# BendulumClockBoard.net
KiCad netlist of a schematic drawn in EAGLE
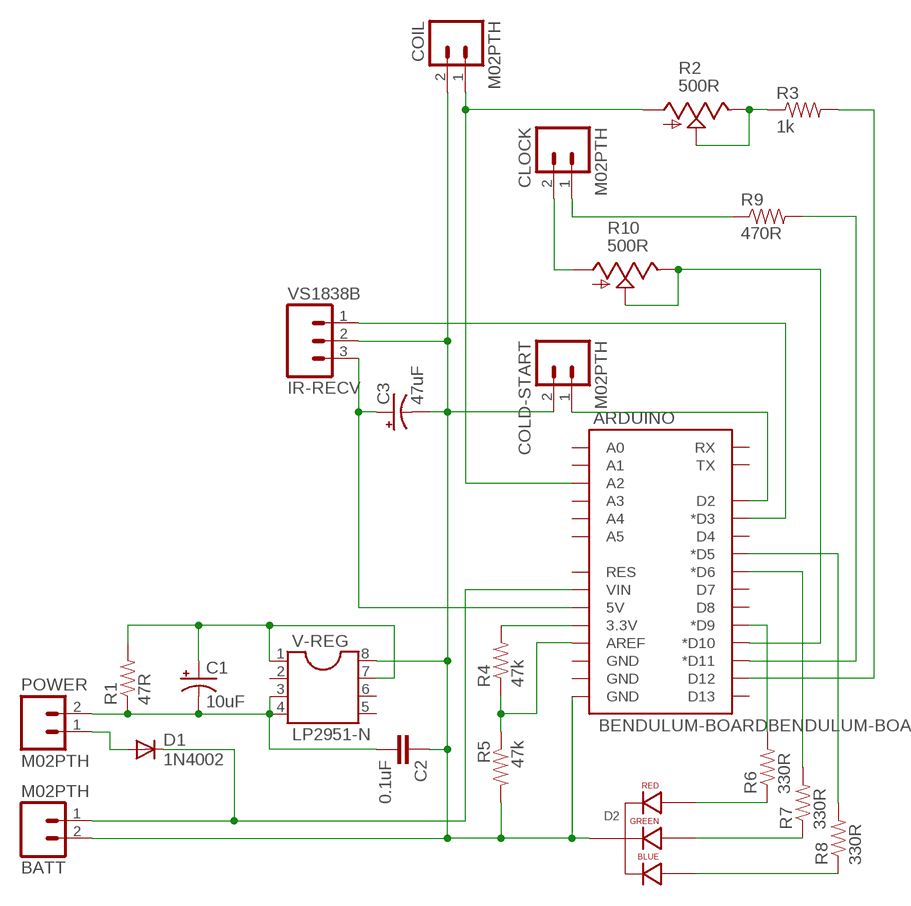
[diagram p0: schematic, sheet 1]

(export (version "E")
  (design (tool "Eeschema 10.0.6"))
  (components
    (comp (ref "ARDUINO")
      (value "BENDULUM-BOARDBENDULUM-BOARD-A")
      (footprint "eagle-import:BENDULUM-BOARD")
      (libsource (lib "eagle-import") (part "BENDULUM-BOARDBENDULUM-BOARD-A"))
    )
    (comp (ref "BATT")
      (value "M02PTH")
      (footprint "eagle-import:1X02")
      (libsource (lib "eagle-import") (part "M02PTH"))
    )
    (comp (ref "C1")
      (value "10uF")
      (footprint "eagle-import:CPOL-RADIAL-10UF-25V")
      (libsource (lib "eagle-import") (part "10UF-25V-20%(PTH)"))
    )
    (comp (ref "C2")
      (value "0.1uF")
      (footprint "eagle-import:CAP-PTH-SMALL")
      (libsource (lib "eagle-import") (part "CAPPTH"))
    )
    (comp (ref "C3")
      (value "47uF")
      (footprint "eagle-import:CPOL-RADIAL-10UF-25V")
      (libsource (lib "eagle-import") (part "10UF-25V-20%(PTH)"))
    )
    (comp (ref "CLOCK")
      (value "M02PTH")
      (footprint "eagle-import:1X02")
      (libsource (lib "eagle-import") (part "M02PTH"))
    )
    (comp (ref "COIL")
      (value "M02PTH")
      (footprint "eagle-import:1X02")
      (libsource (lib "eagle-import") (part "M02PTH"))
    )
    (comp (ref "COLD-START")
      (value "M02PTH")
      (footprint "eagle-import:1X02")
      (libsource (lib "eagle-import") (part "M02PTH"))
    )
    (comp (ref "D1")
      (value "1N4002")
      (footprint "eagle-import:DIODE-1N4001-KIT")
      (libsource (lib "eagle-import") (part "DIODE"))
    )
    (comp (ref "D2")
      (value "LED-RGB-CC-THRUDIFFUSE")
      (footprint "eagle-import:LED-RGB-THRU")
      (libsource (lib "eagle-import") (part "LED-RGB-CC-THRUDIFFUSE"))
    )
    (comp (ref "IR-RECV")
      (value "VS1838B")
      (footprint "eagle-import:1X03")
      (libsource (lib "eagle-import") (part "M03PTH"))
    )
    (comp (ref "POWER")
      (value "M02PTH")
      (footprint "eagle-import:1X02")
      (libsource (lib "eagle-import") (part "M02PTH"))
    )
    (comp (ref "R1")
      (value "47R")
      (footprint "eagle-import:AXIAL-0.4")
      (libsource (lib "eagle-import") (part "RESISTORPTH-1/4W"))
    )
    (comp (ref "R2")
      (value "500R")
      (footprint "eagle-import:S64Y")
      (libsource (lib "eagle-import") (part "TRIM_US-S64Y"))
    )
    (comp (ref "R3")
      (value "1k")
      (footprint "eagle-import:AXIAL-0.4")
      (libsource (lib "eagle-import") (part "RESISTORPTH-1/4W"))
    )
    (comp (ref "R4")
      (value "47k")
      (footprint "eagle-import:AXIAL-0.4")
      (libsource (lib "eagle-import") (part "RESISTORPTH-1/4W"))
    )
    (comp (ref "R5")
      (value "47k")
      (footprint "eagle-import:AXIAL-0.4")
      (libsource (lib "eagle-import") (part "RESISTORPTH-1/4W"))
    )
    (comp (ref "R6")
      (value "330R")
      (footprint "eagle-import:AXIAL-0.4")
      (libsource (lib "eagle-import") (part "RESISTORPTH-1/4W"))
    )
    (comp (ref "R7")
      (value "330R")
      (footprint "eagle-import:AXIAL-0.4")
      (libsource (lib "eagle-import") (part "RESISTORPTH-1/4W"))
    )
    (comp (ref "R8")
      (value "330R")
      (footprint "eagle-import:AXIAL-0.4")
      (libsource (lib "eagle-import") (part "RESISTORPTH-1/4W"))
    )
    (comp (ref "R9")
      (value "470R")
      (footprint "eagle-import:AXIAL-0.4")
      (libsource (lib "eagle-import") (part "RESISTORPTH-1/4W"))
    )
    (comp (ref "R10")
      (value "500R")
      (footprint "eagle-import:S64Y")
      (libsource (lib "eagle-import") (part "TRIM_US-S64Y"))
    )
    (comp (ref "V-REG")
      (value "LP2951-N")
      (footprint "eagle-import:SOCKET-08")
      (libsource (lib "eagle-import") (part "LP2951-N"))
    )
  )
  (nets
    (net (code "1") (name "Net-(ARDUINO-*D3)") (class "Default")
      (node (ref "ARDUINO") (pin "D3") (pinfunction "*D3_D3") (pintype "bidirectional"))
      (node (ref "IR-RECV") (pin "1") (pinfunction "1_1") (pintype "passive"))
    )
    (net (code "2") (name "Net-(ARDUINO-*D5)") (class "Default")
      (node (ref "ARDUINO") (pin "D5") (pinfunction "*D5_D5") (pintype "bidirectional"))
      (node (ref "R8") (pin "P$2") (pinfunction "2_P$2") (pintype "passive"))
    )
    (net (code "3") (name "Net-(ARDUINO-*D6)") (class "Default")
      (node (ref "ARDUINO") (pin "D6") (pinfunction "*D6_D6") (pintype "bidirectional"))
      (node (ref "R7") (pin "P$2") (pinfunction "2_P$2") (pintype "passive"))
    )
    (net (code "4") (name "Net-(ARDUINO-*D9)") (class "Default")
      (node (ref "ARDUINO") (pin "D9") (pinfunction "*D9_D9") (pintype "bidirectional"))
      (node (ref "R6") (pin "P$2") (pinfunction "2_P$2") (pintype "passive"))
    )
    (net (code "5") (name "Net-(ARDUINO-*D10)") (class "Default")
      (node (ref "ARDUINO") (pin "D10") (pinfunction "*D10_D10") (pintype "bidirectional"))
      (node (ref "R10") (pin "E") (pinfunction "E_E") (pintype "passive"))
      (node (ref "R10") (pin "S") (pinfunction "S_S") (pintype "passive"))
    )
    (net (code "6") (name "Net-(ARDUINO-*D11)") (class "Default")
      (node (ref "ARDUINO") (pin "D11") (pinfunction "*D11_D11") (pintype "bidirectional"))
      (node (ref "R9") (pin "P$2") (pinfunction "2_P$2") (pintype "passive"))
    )
    (net (code "7") (name "Net-(ARDUINO-PadA2)") (class "Default")
      (node (ref "ARDUINO") (pin "A2") (pinfunction "A2_A2") (pintype "bidirectional"))
      (node (ref "COIL") (pin "1") (pinfunction "1_1") (pintype "passive"))
      (node (ref "R2") (pin "A") (pinfunction "A_A") (pintype "passive"))
    )
    (net (code "8") (name "Net-(ARDUINO-PadD2)") (class "Default")
      (node (ref "ARDUINO") (pin "D2") (pinfunction "D2_D2") (pintype "bidirectional"))
      (node (ref "COLD-START") (pin "1") (pinfunction "1_1") (pintype "passive"))
    )
    (net (code "9") (name "Net-(ARDUINO-PadVIN)") (class "Default")
      (node (ref "ARDUINO") (pin "VIN") (pinfunction "VIN_VIN") (pintype "bidirectional"))
      (node (ref "BATT") (pin "1") (pinfunction "1_1") (pintype "passive"))
      (node (ref "D1") (pin "C") (pinfunction "C_C") (pintype "passive"))
    )
    (net (code "10") (name "Net-(C1-+)") (class "Default")
      (node (ref "C1") (pin "1") (pinfunction "+_1") (pintype "passive"))
      (node (ref "R1") (pin "P$2") (pinfunction "2_P$2") (pintype "passive"))
      (node (ref "V-REG") (pin "1") (pinfunction "OUTPUT_1") (pintype "passive"))
      (node (ref "V-REG") (pin "7") (pinfunction "FEEDBACK_7") (pintype "passive"))
    )
    (net (code "11") (name "Net-(C1--)") (class "Default")
      (node (ref "C1") (pin "2") (pinfunction "-_2") (pintype "passive"))
      (node (ref "C2") (pin "2") (pinfunction "2_2") (pintype "passive"))
      (node (ref "POWER") (pin "2") (pinfunction "2_2") (pintype "passive"))
      (node (ref "R1") (pin "P$1") (pinfunction "1_P$1") (pintype "passive"))
      (node (ref "V-REG") (pin "3") (pinfunction "SHUTDOWN_3") (pintype "passive"))
      (node (ref "V-REG") (pin "4") (pinfunction "GND_4") (pintype "passive"))
    )
    (net (code "12") (name "Net-(C3-+)") (class "Default")
      (node (ref "ARDUINO") (pin "5V") (pinfunction "5V_5V") (pintype "bidirectional"))
      (node (ref "C3") (pin "1") (pinfunction "+_1") (pintype "passive"))
      (node (ref "IR-RECV") (pin "3") (pinfunction "3_3") (pintype "passive"))
    )
    (net (code "13") (name "Net-(C3--)") (class "Default")
      (node (ref "ARDUINO") (pin "GND@0") (pinfunction "GND_GND@0") (pintype "bidirectional"))
      (node (ref "BATT") (pin "2") (pinfunction "2_2") (pintype "passive"))
      (node (ref "C2") (pin "1") (pinfunction "1_1") (pintype "passive"))
      (node (ref "C3") (pin "2") (pinfunction "-_2") (pintype "passive"))
      (node (ref "COIL") (pin "2") (pinfunction "2_2") (pintype "passive"))
      (node (ref "COLD-START") (pin "2") (pinfunction "2_2") (pintype "passive"))
      (node (ref "D2") (pin "2") (pinfunction "CATHODE_2") (pintype "bidirectional"))
      (node (ref "IR-RECV") (pin "2") (pinfunction "2_2") (pintype "passive"))
      (node (ref "R5") (pin "P$2") (pinfunction "2_P$2") (pintype "passive"))
      (node (ref "V-REG") (pin "8") (pinfunction "INPUT_8") (pintype "passive"))
    )
    (net (code "14") (name "Net-(CLOCK-Pad2)") (class "Default")
      (node (ref "CLOCK") (pin "2") (pinfunction "2_2") (pintype "passive"))
      (node (ref "R10") (pin "A") (pinfunction "A_A") (pintype "passive"))
    )
    (net (code "15") (name "Net-(D1-PadA)") (class "Default")
      (node (ref "D1") (pin "A") (pinfunction "A_A") (pintype "passive"))
      (node (ref "POWER") (pin "1") (pinfunction "1_1") (pintype "passive"))
    )
    (net (code "16") (name "Net-(D2-BLUE_ANODE)") (class "Default")
      (node (ref "D2") (pin "4") (pinfunction "BLUE_ANODE_4") (pintype "bidirectional"))
      (node (ref "R8") (pin "P$1") (pinfunction "1_P$1") (pintype "passive"))
    )
    (net (code "17") (name "Net-(D2-GREEN_ANODE)") (class "Default")
      (node (ref "D2") (pin "3") (pinfunction "GREEN_ANODE_3") (pintype "bidirectional"))
      (node (ref "R7") (pin "P$1") (pinfunction "1_P$1") (pintype "passive"))
    )
    (net (code "18") (name "Net-(D2-RED_ANODE)") (class "Default")
      (node (ref "D2") (pin "1") (pinfunction "RED_ANODE_1") (pintype "bidirectional"))
      (node (ref "R6") (pin "P$1") (pinfunction "1_P$1") (pintype "passive"))
    )
    (net (code "19") (name "Net-(R3-1)") (class "Default")
      (node (ref "R2") (pin "E") (pinfunction "E_E") (pintype "passive"))
      (node (ref "R2") (pin "S") (pinfunction "S_S") (pintype "passive"))
      (node (ref "R3") (pin "P$1") (pinfunction "1_P$1") (pintype "passive"))
    )
    (net (code "20") (name "Net-(R3-2)") (class "Default")
      (node (ref "ARDUINO") (pin "D12") (pinfunction "D12_D12") (pintype "bidirectional"))
      (node (ref "R3") (pin "P$2") (pinfunction "2_P$2") (pintype "passive"))
    )
    (net (code "21") (name "Net-(R4-1)") (class "Default")
      (node (ref "ARDUINO") (pin "AREF") (pinfunction "AREF_AREF") (pintype "bidirectional"))
      (node (ref "R4") (pin "P$1") (pinfunction "1_P$1") (pintype "passive"))
      (node (ref "R5") (pin "P$1") (pinfunction "1_P$1") (pintype "passive"))
    )
    (net (code "22") (name "Net-(R4-2)") (class "Default")
      (node (ref "ARDUINO") (pin "3.3V") (pinfunction "3.3V_3.3V") (pintype "bidirectional"))
      (node (ref "R4") (pin "P$2") (pinfunction "2_P$2") (pintype "passive"))
    )
    (net (code "23") (name "Net-(R9-1)") (class "Default")
      (node (ref "CLOCK") (pin "1") (pinfunction "1_1") (pintype "passive"))
      (node (ref "R9") (pin "P$1") (pinfunction "1_P$1") (pintype "passive"))
    )
    (net (code "24") (name "unconnected-(ARDUINO-GND-PadGND@1)") (class "Default")
      (node (ref "ARDUINO") (pin "GND@1") (pinfunction "GND_GND@1") (pintype "bidirectional"))
    )
    (net (code "25") (name "unconnected-(ARDUINO-GND-PadGND@2)") (class "Default")
      (node (ref "ARDUINO") (pin "GND@2") (pinfunction "GND_GND@2") (pintype "bidirectional"))
    )
    (net (code "26") (name "unconnected-(ARDUINO-PadA0)") (class "Default")
      (node (ref "ARDUINO") (pin "A0") (pinfunction "A0_A0") (pintype "bidirectional"))
    )
    (net (code "27") (name "unconnected-(ARDUINO-PadA1)") (class "Default")
      (node (ref "ARDUINO") (pin "A1") (pinfunction "A1_A1") (pintype "bidirectional"))
    )
    (net (code "28") (name "unconnected-(ARDUINO-PadA3)") (class "Default")
      (node (ref "ARDUINO") (pin "A3") (pinfunction "A3_A3") (pintype "bidirectional"))
    )
    (net (code "29") (name "unconnected-(ARDUINO-PadA4)") (class "Default")
      (node (ref "ARDUINO") (pin "A4") (pinfunction "A4_A4") (pintype "bidirectional"))
    )
    (net (code "30") (name "unconnected-(ARDUINO-PadA5)") (class "Default")
      (node (ref "ARDUINO") (pin "A5") (pinfunction "A5_A5") (pintype "bidirectional"))
    )
    (net (code "31") (name "unconnected-(ARDUINO-PadD4)") (class "Default")
      (node (ref "ARDUINO") (pin "D4") (pinfunction "D4_D4") (pintype "bidirectional"))
    )
    (net (code "32") (name "unconnected-(ARDUINO-PadD7)") (class "Default")
      (node (ref "ARDUINO") (pin "D7") (pinfunction "D7_D7") (pintype "bidirectional"))
    )
    (net (code "33") (name "unconnected-(ARDUINO-PadD8)") (class "Default")
      (node (ref "ARDUINO") (pin "D8") (pinfunction "D8_D8") (pintype "bidirectional"))
    )
    (net (code "34") (name "unconnected-(ARDUINO-PadD13)") (class "Default")
      (node (ref "ARDUINO") (pin "D13") (pinfunction "D13_D13") (pintype "bidirectional"))
    )
    (net (code "35") (name "unconnected-(ARDUINO-PadRES)") (class "Default")
      (node (ref "ARDUINO") (pin "RES") (pinfunction "RES_RES") (pintype "bidirectional"))
    )
    (net (code "36") (name "unconnected-(ARDUINO-PadRX)") (class "Default")
      (node (ref "ARDUINO") (pin "RX") (pinfunction "RX_RX") (pintype "bidirectional"))
    )
    (net (code "37") (name "unconnected-(ARDUINO-PadTX)") (class "Default")
      (node (ref "ARDUINO") (pin "TX") (pinfunction "TX_TX") (pintype "bidirectional"))
    )
    (net (code "38") (name "unconnected-(V-REG-NOT-ERROR-Pad5)") (class "Default")
      (node (ref "V-REG") (pin "5") (pinfunction "NOT-ERROR_5") (pintype "passive"))
    )
    (net (code "39") (name "unconnected-(V-REG-SENSE-Pad2)") (class "Default")
      (node (ref "V-REG") (pin "2") (pinfunction "SENSE_2") (pintype "passive"))
    )
    (net (code "40") (name "unconnected-(V-REG-V0-TAP-Pad6)") (class "Default")
      (node (ref "V-REG") (pin "6") (pinfunction "V0-TAP_6") (pintype "passive"))
    )
  )
)
